# dc_sensor_v2.net
KiCad netlist of a schematic drawn in EAGLE
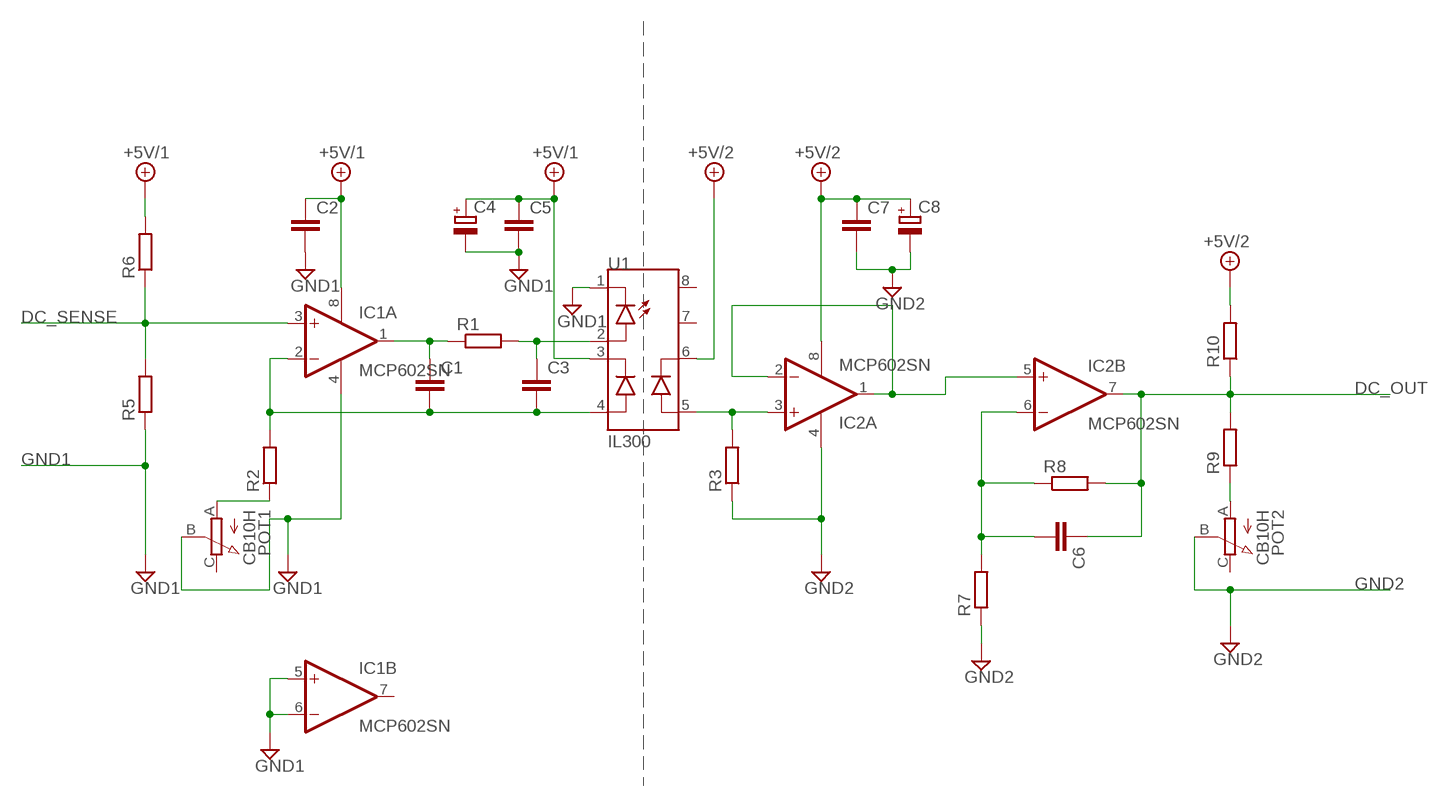
[diagram p0: schematic, sheet 1]

(export (version "E")
  (design (tool "Eeschema 10.0.6"))
  (components
    (comp (ref "C1")
      (value "C-EU025-040X050")
      (footprint "eagle-import:C025-040X050")
      (libsource (lib "eagle-import") (part "C-EU025-040X050"))
    )
    (comp (ref "C2")
      (value "C-EU025-040X050")
      (footprint "eagle-import:C025-040X050")
      (libsource (lib "eagle-import") (part "C-EU025-040X050"))
    )
    (comp (ref "C3")
      (value "C-EU025-040X050")
      (footprint "eagle-import:C025-040X050")
      (libsource (lib "eagle-import") (part "C-EU025-040X050"))
    )
    (comp (ref "C4")
      (value "CPOL-EUE2-5")
      (footprint "eagle-import:E2-5")
      (libsource (lib "eagle-import") (part "CPOL-EUE2-5"))
    )
    (comp (ref "C5")
      (value "C-EU025-040X050")
      (footprint "eagle-import:C025-040X050")
      (libsource (lib "eagle-import") (part "C-EU025-040X050"))
    )
    (comp (ref "C6")
      (value "C-EU025-040X050")
      (footprint "eagle-import:C025-040X050")
      (libsource (lib "eagle-import") (part "C-EU025-040X050"))
    )
    (comp (ref "C7")
      (value "C-EU025-040X050")
      (footprint "eagle-import:C025-040X050")
      (libsource (lib "eagle-import") (part "C-EU025-040X050"))
    )
    (comp (ref "C8")
      (value "CPOL-EUE2-5")
      (footprint "eagle-import:E2-5")
      (libsource (lib "eagle-import") (part "CPOL-EUE2-5"))
    )
    (comp (ref "IC1")
      (value "MCP602SN")
      (footprint "eagle-import:SO08")
      (libsource (lib "eagle-import") (part "MCP602SN"))
    )
    (comp (ref "IC2")
      (value "MCP602SN")
      (footprint "eagle-import:SO08")
      (libsource (lib "eagle-import") (part "MCP602SN"))
    )
    (comp (ref "POT1")
      (value "CB10H")
      (footprint "eagle-import:CB10V")
      (libsource (lib "eagle-import") (part "CB10H"))
    )
    (comp (ref "POT2")
      (value "CB10H")
      (footprint "eagle-import:CB10V")
      (libsource (lib "eagle-import") (part "CB10H"))
    )
    (comp (ref "R1")
      (value "R-EU_0207/10")
      (footprint "eagle-import:0207_10")
      (libsource (lib "eagle-import") (part "R-EU_0207/10"))
    )
    (comp (ref "R2")
      (value "R-EU_0207/10")
      (footprint "eagle-import:0207_10")
      (libsource (lib "eagle-import") (part "R-EU_0207/10"))
    )
    (comp (ref "R3")
      (value "R-EU_0207/10")
      (footprint "eagle-import:0207_10")
      (libsource (lib "eagle-import") (part "R-EU_0207/10"))
    )
    (comp (ref "R5")
      (value "R-EU_0207/10")
      (footprint "eagle-import:0207_10")
      (libsource (lib "eagle-import") (part "R-EU_0207/10"))
    )
    (comp (ref "R6")
      (value "R-EU_0207/10")
      (footprint "eagle-import:0207_10")
      (libsource (lib "eagle-import") (part "R-EU_0207/10"))
    )
    (comp (ref "R7")
      (value "R-EU_0207/10")
      (footprint "eagle-import:0207_10")
      (libsource (lib "eagle-import") (part "R-EU_0207/10"))
    )
    (comp (ref "R8")
      (value "R-EU_0207/10")
      (footprint "eagle-import:0207_10")
      (libsource (lib "eagle-import") (part "R-EU_0207/10"))
    )
    (comp (ref "R9")
      (value "R-EU_0207/10")
      (footprint "eagle-import:0207_10")
      (libsource (lib "eagle-import") (part "R-EU_0207/10"))
    )
    (comp (ref "R10")
      (value "R-EU_0207/10")
      (footprint "eagle-import:0207_10")
      (libsource (lib "eagle-import") (part "R-EU_0207/10"))
    )
    (comp (ref "U1")
      (value "IL300")
      (footprint "eagle-import:DIL08")
      (libsource (lib "eagle-import") (part "IL300"))
    )
  )
  (nets
    (net (code "1") (name "+5V{slash}1") (class "Default")
      (node (ref "C2") (pin "1") (pinfunction "1_1") (pintype "passive"))
      (node (ref "C4") (pin "+") (pinfunction "+_+") (pintype "passive"))
      (node (ref "C5") (pin "1") (pinfunction "1_1") (pintype "passive"))
      (node (ref "IC1") (pin "8") (pinfunction "V+_8") (pintype "power_in"))
      (node (ref "R6") (pin "2") (pinfunction "2_2") (pintype "passive"))
      (node (ref "U1") (pin "3") (pinfunction "C_FB_3") (pintype "passive"))
    )
    (net (code "2") (name "+5V{slash}2") (class "Default")
      (node (ref "C7") (pin "1") (pinfunction "1_1") (pintype "passive"))
      (node (ref "C8") (pin "+") (pinfunction "+_+") (pintype "passive"))
      (node (ref "IC2") (pin "8") (pinfunction "V+_8") (pintype "power_in"))
      (node (ref "R10") (pin "2") (pinfunction "2_2") (pintype "passive"))
      (node (ref "U1") (pin "6") (pinfunction "C_OUT_6") (pintype "passive"))
    )
    (net (code "3") (name "/DC_OUT") (class "Default")
      (node (ref "C6") (pin "1") (pinfunction "1_1") (pintype "passive"))
      (node (ref "IC2") (pin "7") (pinfunction "OUT_7") (pintype "output"))
      (node (ref "R10") (pin "1") (pinfunction "1_1") (pintype "passive"))
      (node (ref "R8") (pin "2") (pinfunction "2_2") (pintype "passive"))
      (node (ref "R9") (pin "2") (pinfunction "2_2") (pintype "passive"))
    )
    (net (code "4") (name "/DC_SENSE") (class "Default")
      (node (ref "IC1") (pin "3") (pinfunction "+IN_3") (pintype "input"))
      (node (ref "R5") (pin "2") (pinfunction "2_2") (pintype "passive"))
      (node (ref "R6") (pin "1") (pinfunction "1_1") (pintype "passive"))
    )
    (net (code "5") (name "GND1") (class "Default")
      (node (ref "C2") (pin "2") (pinfunction "2_2") (pintype "passive"))
      (node (ref "C4") (pin "-") (pinfunction "-_-") (pintype "passive"))
      (node (ref "C5") (pin "2") (pinfunction "2_2") (pintype "passive"))
      (node (ref "IC1") (pin "4") (pinfunction "V-_4") (pintype "power_in"))
      (node (ref "IC1") (pin "5") (pinfunction "+IN_5") (pintype "input"))
      (node (ref "IC1") (pin "6") (pinfunction "-IN_6") (pintype "input"))
      (node (ref "POT1") (pin "B") (pinfunction "S_B") (pintype "passive"))
      (node (ref "R5") (pin "1") (pinfunction "1_1") (pintype "passive"))
      (node (ref "U1") (pin "1") (pinfunction "C_LED_1") (pintype "passive"))
    )
    (net (code "6") (name "GND2") (class "Default")
      (node (ref "C7") (pin "2") (pinfunction "2_2") (pintype "passive"))
      (node (ref "C8") (pin "-") (pinfunction "-_-") (pintype "passive"))
      (node (ref "IC2") (pin "4") (pinfunction "V-_4") (pintype "power_in"))
      (node (ref "POT2") (pin "B") (pinfunction "S_B") (pintype "passive"))
      (node (ref "R3") (pin "1") (pinfunction "1_1") (pintype "passive"))
      (node (ref "R7") (pin "1") (pinfunction "1_1") (pintype "passive"))
    )
    (net (code "7") (name "Net-(IC1A--IN)") (class "Default")
      (node (ref "C1") (pin "2") (pinfunction "2_2") (pintype "passive"))
      (node (ref "C3") (pin "2") (pinfunction "2_2") (pintype "passive"))
      (node (ref "IC1") (pin "2") (pinfunction "-IN_2") (pintype "input"))
      (node (ref "R2") (pin "2") (pinfunction "2_2") (pintype "passive"))
      (node (ref "U1") (pin "4") (pinfunction "A_FB_4") (pintype "passive"))
    )
    (net (code "8") (name "Net-(IC1A-OUT)") (class "Default")
      (node (ref "C1") (pin "1") (pinfunction "1_1") (pintype "passive"))
      (node (ref "IC1") (pin "1") (pinfunction "OUT_1") (pintype "output"))
      (node (ref "R1") (pin "1") (pinfunction "1_1") (pintype "passive"))
    )
    (net (code "9") (name "Net-(IC2A-+IN)") (class "Default")
      (node (ref "IC2") (pin "3") (pinfunction "+IN_3") (pintype "input"))
      (node (ref "R3") (pin "2") (pinfunction "2_2") (pintype "passive"))
      (node (ref "U1") (pin "5") (pinfunction "A_OUT_5") (pintype "passive"))
    )
    (net (code "10") (name "Net-(IC2A--IN)") (class "Default")
      (node (ref "IC2") (pin "1") (pinfunction "OUT_1") (pintype "output"))
      (node (ref "IC2") (pin "2") (pinfunction "-IN_2") (pintype "input"))
      (node (ref "IC2") (pin "5") (pinfunction "+IN_5") (pintype "input"))
    )
    (net (code "11") (name "Net-(IC2B--IN)") (class "Default")
      (node (ref "C6") (pin "2") (pinfunction "2_2") (pintype "passive"))
      (node (ref "IC2") (pin "6") (pinfunction "-IN_6") (pintype "input"))
      (node (ref "R7") (pin "2") (pinfunction "2_2") (pintype "passive"))
      (node (ref "R8") (pin "1") (pinfunction "1_1") (pintype "passive"))
    )
    (net (code "12") (name "Net-(POT1-PadA)") (class "Default")
      (node (ref "POT1") (pin "A") (pinfunction "A_A") (pintype "passive"))
      (node (ref "R2") (pin "1") (pinfunction "1_1") (pintype "passive"))
    )
    (net (code "13") (name "Net-(POT2-PadA)") (class "Default")
      (node (ref "POT2") (pin "A") (pinfunction "A_A") (pintype "passive"))
      (node (ref "R9") (pin "1") (pinfunction "1_1") (pintype "passive"))
    )
    (net (code "14") (name "Net-(U1-A_LED)") (class "Default")
      (node (ref "C3") (pin "1") (pinfunction "1_1") (pintype "passive"))
      (node (ref "R1") (pin "2") (pinfunction "2_2") (pintype "passive"))
      (node (ref "U1") (pin "2") (pinfunction "A_LED_2") (pintype "passive"))
    )
    (net (code "15") (name "unconnected-(IC1B-OUT-Pad7)") (class "Default")
      (node (ref "IC1") (pin "7") (pinfunction "OUT_7") (pintype "output"))
    )
    (net (code "16") (name "unconnected-(POT1-E-PadC)") (class "Default")
      (node (ref "POT1") (pin "C") (pinfunction "E_C") (pintype "passive"))
    )
    (net (code "17") (name "unconnected-(POT2-E-PadC)") (class "Default")
      (node (ref "POT2") (pin "C") (pinfunction "E_C") (pintype "passive"))
    )
    (net (code "18") (name "unconnected-(U1-PIN7-Pad7)") (class "Default")
      (node (ref "U1") (pin "7") (pinfunction "PIN7_7") (pintype "no_connect"))
    )
    (net (code "19") (name "unconnected-(U1-PIN8-Pad8)") (class "Default")
      (node (ref "U1") (pin "8") (pinfunction "PIN8_8") (pintype "no_connect"))
    )
  )
)
